# AnalogInterface2.net
KiCad netlist of a schematic drawn in Altium Designer
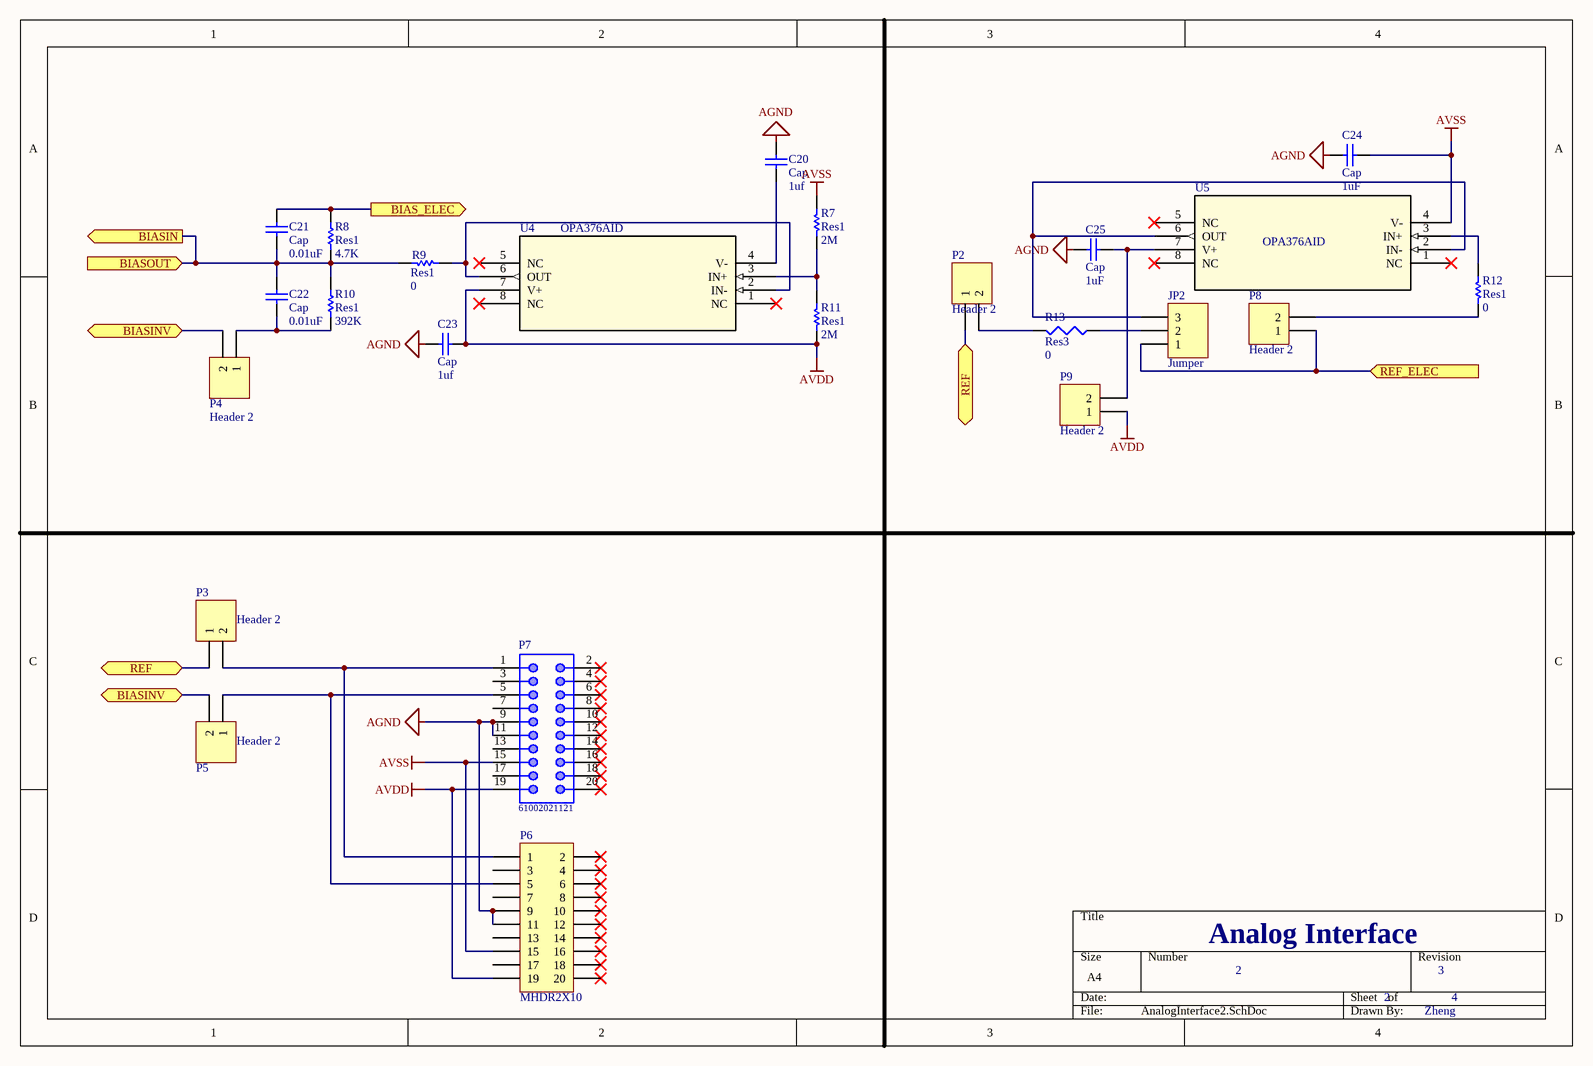
[diagram p0: AnalogInterface2.SchDoc]

(export (version "E")
  (design (tool "Eeschema 10.0.6"))
  (components
    (comp (ref "C20")
      (value "Cap")
      (footprint "0402C")
      (description "Capacitor")
      (fields (field (name "ALTIUM_VALUE") "1uf") (field (name "PUBLISHER") "Altium Limited"))
      (libsource (lib "Miscellaneous Devices") (part "Cap"))
    )
    (comp (ref "C21")
      (value "Cap")
      (footprint "0402C")
      (description "Capacitor")
      (fields (field (name "ALTIUM_VALUE") "0.01uF") (field (name "PUBLISHER") "Altium Limited"))
      (libsource (lib "Miscellaneous Devices") (part "Cap"))
    )
    (comp (ref "C22")
      (value "Cap")
      (footprint "0402C")
      (description "Capacitor")
      (fields (field (name "ALTIUM_VALUE") "0.01uF") (field (name "PUBLISHER") "Altium Limited"))
      (libsource (lib "Miscellaneous Devices") (part "Cap"))
    )
    (comp (ref "C23")
      (value "Cap")
      (footprint "0402C")
      (description "Capacitor")
      (fields (field (name "ALTIUM_VALUE") "1uf") (field (name "PUBLISHER") "Altium Limited"))
      (libsource (lib "Miscellaneous Devices") (part "Cap"))
    )
    (comp (ref "C24")
      (value "Cap")
      (footprint "0402C")
      (description "Capacitor")
      (fields (field (name "ALTIUM_VALUE") "1uF") (field (name "PUBLISHER") "Altium Limited"))
      (libsource (lib "Miscellaneous Devices") (part "Cap"))
    )
    (comp (ref "C25")
      (value "Cap")
      (footprint "0402C")
      (description "Capacitor")
      (fields (field (name "ALTIUM_VALUE") "1uF") (field (name "PUBLISHER") "Altium Limited"))
      (libsource (lib "Miscellaneous Devices") (part "Cap"))
    )
    (comp (ref "JP2")
      (value "Jumper")
      (footprint "HDR1X3")
      (description "Header, 3-Pin")
      (fields (field (name "PUBLISHER") "Altium Limited"))
      (libsource (lib "Miscellaneous Connectors") (part "Header 3"))
    )
    (comp (ref "P2")
      (value "Header 2")
      (footprint "HDR1X2")
      (description "Header, 2-Pin")
      (fields (field (name "PUBLISHER") "Altium Limited"))
      (libsource (lib "") (part "Header 2_2"))
    )
    (comp (ref "P3")
      (value "Header 2")
      (footprint "HDR1X2")
      (description "Header, 2-Pin")
      (fields (field (name "PUBLISHER") "Altium Limited"))
      (libsource (lib "") (part "Header 2_2"))
    )
    (comp (ref "P4")
      (value "Header 2")
      (footprint "HDR1X2")
      (description "Header, 2-Pin")
      (fields (field (name "PUBLISHER") "Altium Limited"))
      (libsource (lib "Miscellaneous Connectors") (part "Header 2"))
    )
    (comp (ref "P5")
      (value "Header 2")
      (footprint "HDR1X2")
      (description "Header, 2-Pin")
      (fields (field (name "PUBLISHER") "Altium Limited"))
      (libsource (lib "Miscellaneous Connectors") (part "Header 2"))
    )
    (comp (ref "P6")
      (value "MHDR2X10")
      (footprint "HDR2.54-M-LS-2x10P")
      (description "Header, 10-Pin, Dual row")
      (fields (field (name "PUBLISHER") "Altium Limited"))
      (libsource (lib "Miscellaneous Connectors") (part "MHDR2X10"))
    )
    (comp (ref "P7")
      (value "61002021121")
      (footprint "61002021121")
      (description "SMT Vertical Pin Header WR-PHD, Pitch 2.54 mm, Dual Row, 20 pins")
      (fields (field (name "PUBLISHER") "Wurth Elektronik"))
      (libsource (lib "Pin Header WR-PHD_2.54 mm") (part "61002021121"))
    )
    (comp (ref "P8")
      (value "Header 2")
      (footprint "HDR1X2")
      (description "Header, 2-Pin")
      (fields (field (name "PUBLISHER") "Altium Limited"))
      (libsource (lib "") (part "Header 2_1"))
    )
    (comp (ref "P9")
      (value "Header 2")
      (footprint "HDR1X2")
      (description "Header, 2-Pin")
      (fields (field (name "PUBLISHER") "Altium Limited"))
      (libsource (lib "") (part "Header 2_1"))
    )
    (comp (ref "R7")
      (value "Res1")
      (footprint "0603")
      (description "Resistor")
      (fields (field (name "ALTIUM_VALUE") "2M") (field (name "PUBLISHER") "Altium Limited"))
      (libsource (lib "Miscellaneous Devices") (part "Res1"))
    )
    (comp (ref "R8")
      (value "Res1")
      (footprint "0603")
      (description "Resistor")
      (fields (field (name "ALTIUM_VALUE") "4.7K") (field (name "PUBLISHER") "Altium Limited"))
      (libsource (lib "Miscellaneous Devices") (part "Res1"))
    )
    (comp (ref "R9")
      (value "Res1")
      (footprint "0603")
      (description "Resistor")
      (fields (field (name "ALTIUM_VALUE") "0") (field (name "PUBLISHER") "Altium Limited"))
      (libsource (lib "Miscellaneous Devices") (part "Res1"))
    )
    (comp (ref "R10")
      (value "Res1")
      (footprint "0603")
      (description "Resistor")
      (fields (field (name "ALTIUM_VALUE") "392K") (field (name "PUBLISHER") "Altium Limited"))
      (libsource (lib "Miscellaneous Devices") (part "Res1"))
    )
    (comp (ref "R11")
      (value "Res1")
      (footprint "0603")
      (description "Resistor")
      (fields (field (name "ALTIUM_VALUE") "2M") (field (name "PUBLISHER") "Altium Limited"))
      (libsource (lib "Miscellaneous Devices") (part "Res1"))
    )
    (comp (ref "R12")
      (value "Res1")
      (footprint "0603")
      (description "Resistor")
      (fields (field (name "ALTIUM_VALUE") "0") (field (name "PUBLISHER") "Altium Limited"))
      (libsource (lib "Miscellaneous Devices") (part "Res1"))
    )
    (comp (ref "R13")
      (value "Res3")
      (footprint "0603")
      (description "Resistor")
      (fields (field (name "ALTIUM_VALUE") "0") (field (name "PUBLISHER") "Altium Limited"))
      (libsource (lib "Miscellaneous Devices") (part "Res3"))
    )
    (comp (ref "U4")
      (value "OPA376AID")
      (footprint "SOIC8")
      (description "Precision, Low Noise, Low Iq Operational Amplifier")
      (fields
        (field (name "MANUFACTURER") "Texas Instruments")
        (field (name "GENERIC_PART_NUMBER") "OPA376")
        (field (name "COPYRIGHT") "Copyright (C) 2018 Accelerated Designs. All rights reserved")
      )
      (libsource (lib "2020-11-25_03-34-00") (part "OPA376AID"))
    )
    (comp (ref "U5")
      (value "OPA376AID")
      (footprint "SOIC8")
      (description "Precision, Low Noise, Low Iq Operational Amplifier")
      (fields
        (field (name "MANUFACTURER") "Texas Instruments")
        (field (name "GENERIC_PART_NUMBER") "OPA376")
        (field (name "COPYRIGHT") "Copyright (C) 2018 Accelerated Designs. All rights reserved")
      )
      (libsource (lib "2020-11-25_03-34-00") (part "OPA376AID"))
    )
  )
  (nets
    (net (code "1") (name "/BIASIN") (class "Default")
      (node (ref "C21") (pin "1") (pinfunction "1_1") (pintype "passive"))
      (node (ref "C22") (pin "2") (pinfunction "2_2") (pintype "passive"))
      (node (ref "R10") (pin "1") (pinfunction "1_1") (pintype "passive"))
      (node (ref "R8") (pin "2") (pinfunction "2_2") (pintype "passive"))
      (node (ref "R9") (pin "1") (pinfunction "1_1") (pintype "passive"))
    )
    (net (code "2") (name "/BIASINV") (class "Default")
      (node (ref "P4") (pin "2") (pinfunction "2_2") (pintype "passive"))
      (node (ref "P5") (pin "2") (pinfunction "2_2") (pintype "passive"))
    )
    (net (code "3") (name "/BIAS_ELEC") (class "Default")
      (node (ref "C21") (pin "2") (pinfunction "2_2") (pintype "passive"))
      (node (ref "R8") (pin "1") (pinfunction "1_1") (pintype "passive"))
    )
    (net (code "4") (name "/REF") (class "Default")
      (node (ref "P2") (pin "1") (pinfunction "1_1") (pintype "passive"))
      (node (ref "P3") (pin "1") (pinfunction "1_1") (pintype "passive"))
    )
    (net (code "5") (name "/REF_ELEC") (class "Default")
      (node (ref "JP2") (pin "1") (pinfunction "1_1") (pintype "passive"))
      (node (ref "P8") (pin "1") (pinfunction "1_1") (pintype "passive"))
    )
    (net (code "6") (name "AGND") (class "Default")
      (node (ref "C20") (pin "1") (pinfunction "1_1") (pintype "passive"))
      (node (ref "C23") (pin "1") (pinfunction "1_1") (pintype "passive"))
      (node (ref "C24") (pin "2") (pinfunction "2_2") (pintype "passive"))
      (node (ref "C25") (pin "2") (pinfunction "2_2") (pintype "passive"))
      (node (ref "P6") (pin "11") (pinfunction "11_11") (pintype "passive"))
      (node (ref "P6") (pin "9") (pinfunction "9_9") (pintype "passive"))
      (node (ref "P7") (pin "11") (pinfunction "11_11") (pintype "passive"))
      (node (ref "P7") (pin "9") (pinfunction "9_9") (pintype "passive"))
    )
    (net (code "7") (name "AVDD") (class "Default")
      (node (ref "C23") (pin "2") (pinfunction "2_2") (pintype "passive"))
      (node (ref "P6") (pin "19") (pinfunction "19_19") (pintype "passive"))
      (node (ref "P7") (pin "19") (pinfunction "19_19") (pintype "passive"))
      (node (ref "P9") (pin "1") (pinfunction "1_1") (pintype "passive"))
      (node (ref "R11") (pin "2") (pinfunction "2_2") (pintype "passive"))
      (node (ref "U4") (pin "7") (pinfunction "V+_7") (pintype "power_in"))
    )
    (net (code "8") (name "AVSS") (class "Default")
      (node (ref "C24") (pin "1") (pinfunction "1_1") (pintype "passive"))
      (node (ref "P6") (pin "15") (pinfunction "15_15") (pintype "passive"))
      (node (ref "P7") (pin "15") (pinfunction "15_15") (pintype "passive"))
      (node (ref "R7") (pin "1") (pinfunction "1_1") (pintype "passive"))
      (node (ref "U5") (pin "4") (pinfunction "V-_4") (pintype "power_in"))
    )
    (net (code "9") (name "Net-(C22-Pad1)") (class "Default")
      (node (ref "C22") (pin "1") (pinfunction "1_1") (pintype "passive"))
      (node (ref "P4") (pin "1") (pinfunction "1_1") (pintype "passive"))
      (node (ref "R10") (pin "2") (pinfunction "2_2") (pintype "passive"))
    )
    (net (code "10") (name "Net-(JP2-Pad2)") (class "Default")
      (node (ref "JP2") (pin "2") (pinfunction "2_2") (pintype "passive"))
      (node (ref "R13") (pin "2") (pinfunction "2_2") (pintype "passive"))
    )
    (net (code "11") (name "Net-(P2-Pad2)") (class "Default")
      (node (ref "P2") (pin "2") (pinfunction "2_2") (pintype "passive"))
      (node (ref "R13") (pin "1") (pinfunction "1_1") (pintype "passive"))
    )
    (net (code "12") (name "Net-(P3-Pad2)") (class "Default")
      (node (ref "P3") (pin "2") (pinfunction "2_2") (pintype "passive"))
      (node (ref "P6") (pin "1") (pinfunction "1_1") (pintype "passive"))
      (node (ref "P7") (pin "1") (pinfunction "1_1") (pintype "passive"))
    )
    (net (code "13") (name "Net-(P5-Pad1)") (class "Default")
      (node (ref "P5") (pin "1") (pinfunction "1_1") (pintype "passive"))
      (node (ref "P6") (pin "5") (pinfunction "5_5") (pintype "passive"))
      (node (ref "P7") (pin "5") (pinfunction "5_5") (pintype "passive"))
    )
    (net (code "14") (name "Net-(P8-Pad2)") (class "Default")
      (node (ref "P8") (pin "2") (pinfunction "2_2") (pintype "passive"))
      (node (ref "R12") (pin "1") (pinfunction "1_1") (pintype "passive"))
    )
    (net (code "15") (name "Net-(U4-IN+)") (class "Default")
      (node (ref "R11") (pin "1") (pinfunction "1_1") (pintype "passive"))
      (node (ref "R7") (pin "2") (pinfunction "2_2") (pintype "passive"))
      (node (ref "U4") (pin "3") (pinfunction "IN+_3") (pintype "input"))
    )
    (net (code "16") (name "Net-(U4-IN-)") (class "Default")
      (node (ref "R9") (pin "2") (pinfunction "2_2") (pintype "passive"))
      (node (ref "U4") (pin "2") (pinfunction "IN-_2") (pintype "input"))
      (node (ref "U4") (pin "6") (pinfunction "OUT_6") (pintype "output"))
    )
    (net (code "17") (name "Net-(U4-V-)") (class "Default")
      (node (ref "C20") (pin "2") (pinfunction "2_2") (pintype "passive"))
      (node (ref "U4") (pin "4") (pinfunction "V-_4") (pintype "power_in"))
    )
    (net (code "18") (name "Net-(U5-IN+)") (class "Default")
      (node (ref "R12") (pin "2") (pinfunction "2_2") (pintype "passive"))
      (node (ref "U5") (pin "3") (pinfunction "IN+_3") (pintype "input"))
    )
    (net (code "19") (name "Net-(U5-IN-)") (class "Default")
      (node (ref "JP2") (pin "3") (pinfunction "3_3") (pintype "passive"))
      (node (ref "U5") (pin "2") (pinfunction "IN-_2") (pintype "input"))
      (node (ref "U5") (pin "6") (pinfunction "OUT_6") (pintype "output"))
    )
    (net (code "20") (name "Net-(U5-V+)") (class "Default")
      (node (ref "C25") (pin "1") (pinfunction "1_1") (pintype "passive"))
      (node (ref "P9") (pin "2") (pinfunction "2_2") (pintype "passive"))
      (node (ref "U5") (pin "7") (pinfunction "V+_7") (pintype "power_in"))
    )
    (net (code "21") (name "unconnected-(P6-Pad2)") (class "Default")
      (node (ref "P6") (pin "2") (pinfunction "2_2") (pintype "passive+no_connect"))
    )
    (net (code "22") (name "unconnected-(P6-Pad3)") (class "Default")
      (node (ref "P6") (pin "3") (pinfunction "3_3") (pintype "passive"))
    )
    (net (code "23") (name "unconnected-(P6-Pad4)") (class "Default")
      (node (ref "P6") (pin "4") (pinfunction "4_4") (pintype "passive+no_connect"))
    )
    (net (code "24") (name "unconnected-(P6-Pad6)") (class "Default")
      (node (ref "P6") (pin "6") (pinfunction "6_6") (pintype "passive+no_connect"))
    )
    (net (code "25") (name "unconnected-(P6-Pad7)") (class "Default")
      (node (ref "P6") (pin "7") (pinfunction "7_7") (pintype "passive"))
    )
    (net (code "26") (name "unconnected-(P6-Pad8)") (class "Default")
      (node (ref "P6") (pin "8") (pinfunction "8_8") (pintype "passive+no_connect"))
    )
    (net (code "27") (name "unconnected-(P6-Pad10)") (class "Default")
      (node (ref "P6") (pin "10") (pinfunction "10_10") (pintype "passive+no_connect"))
    )
    (net (code "28") (name "unconnected-(P6-Pad12)") (class "Default")
      (node (ref "P6") (pin "12") (pinfunction "12_12") (pintype "passive+no_connect"))
    )
    (net (code "29") (name "unconnected-(P6-Pad13)") (class "Default")
      (node (ref "P6") (pin "13") (pinfunction "13_13") (pintype "passive"))
    )
    (net (code "30") (name "unconnected-(P6-Pad14)") (class "Default")
      (node (ref "P6") (pin "14") (pinfunction "14_14") (pintype "passive+no_connect"))
    )
    (net (code "31") (name "unconnected-(P6-Pad16)") (class "Default")
      (node (ref "P6") (pin "16") (pinfunction "16_16") (pintype "passive+no_connect"))
    )
    (net (code "32") (name "unconnected-(P6-Pad17)") (class "Default")
      (node (ref "P6") (pin "17") (pinfunction "17_17") (pintype "passive"))
    )
    (net (code "33") (name "unconnected-(P6-Pad18)") (class "Default")
      (node (ref "P6") (pin "18") (pinfunction "18_18") (pintype "passive+no_connect"))
    )
    (net (code "34") (name "unconnected-(P6-Pad20)") (class "Default")
      (node (ref "P6") (pin "20") (pinfunction "20_20") (pintype "passive+no_connect"))
    )
    (net (code "35") (name "unconnected-(P7-Pad2)") (class "Default")
      (node (ref "P7") (pin "2") (pinfunction "2_2") (pintype "passive+no_connect"))
    )
    (net (code "36") (name "unconnected-(P7-Pad3)") (class "Default")
      (node (ref "P7") (pin "3") (pinfunction "3_3") (pintype "passive"))
    )
    (net (code "37") (name "unconnected-(P7-Pad4)") (class "Default")
      (node (ref "P7") (pin "4") (pinfunction "4_4") (pintype "passive+no_connect"))
    )
    (net (code "38") (name "unconnected-(P7-Pad6)") (class "Default")
      (node (ref "P7") (pin "6") (pinfunction "6_6") (pintype "passive+no_connect"))
    )
    (net (code "39") (name "unconnected-(P7-Pad7)") (class "Default")
      (node (ref "P7") (pin "7") (pinfunction "7_7") (pintype "passive"))
    )
    (net (code "40") (name "unconnected-(P7-Pad8)") (class "Default")
      (node (ref "P7") (pin "8") (pinfunction "8_8") (pintype "passive+no_connect"))
    )
    (net (code "41") (name "unconnected-(P7-Pad10)") (class "Default")
      (node (ref "P7") (pin "10") (pinfunction "10_10") (pintype "passive+no_connect"))
    )
    (net (code "42") (name "unconnected-(P7-Pad12)") (class "Default")
      (node (ref "P7") (pin "12") (pinfunction "12_12") (pintype "passive+no_connect"))
    )
    (net (code "43") (name "unconnected-(P7-Pad13)") (class "Default")
      (node (ref "P7") (pin "13") (pinfunction "13_13") (pintype "passive"))
    )
    (net (code "44") (name "unconnected-(P7-Pad14)") (class "Default")
      (node (ref "P7") (pin "14") (pinfunction "14_14") (pintype "passive+no_connect"))
    )
    (net (code "45") (name "unconnected-(P7-Pad16)") (class "Default")
      (node (ref "P7") (pin "16") (pinfunction "16_16") (pintype "passive+no_connect"))
    )
    (net (code "46") (name "unconnected-(P7-Pad17)") (class "Default")
      (node (ref "P7") (pin "17") (pinfunction "17_17") (pintype "passive"))
    )
    (net (code "47") (name "unconnected-(P7-Pad18)") (class "Default")
      (node (ref "P7") (pin "18") (pinfunction "18_18") (pintype "passive+no_connect"))
    )
    (net (code "48") (name "unconnected-(P7-Pad20)") (class "Default")
      (node (ref "P7") (pin "20") (pinfunction "20_20") (pintype "passive+no_connect"))
    )
    (net (code "49") (name "unconnected-(U4-NC-Pad1)") (class "Default")
      (node (ref "U4") (pin "1") (pinfunction "NC_1") (pintype "passive+no_connect"))
    )
    (net (code "50") (name "unconnected-(U4-NC-Pad5)") (class "Default")
      (node (ref "U4") (pin "5") (pinfunction "NC_5") (pintype "passive+no_connect"))
    )
    (net (code "51") (name "unconnected-(U4-NC-Pad8)") (class "Default")
      (node (ref "U4") (pin "8") (pinfunction "NC_8") (pintype "passive+no_connect"))
    )
    (net (code "52") (name "unconnected-(U5-NC-Pad1)") (class "Default")
      (node (ref "U5") (pin "1") (pinfunction "NC_1") (pintype "passive+no_connect"))
    )
    (net (code "53") (name "unconnected-(U5-NC-Pad5)") (class "Default")
      (node (ref "U5") (pin "5") (pinfunction "NC_5") (pintype "passive+no_connect"))
    )
    (net (code "54") (name "unconnected-(U5-NC-Pad8)") (class "Default")
      (node (ref "U5") (pin "8") (pinfunction "NC_8") (pintype "passive+no_connect"))
    )
  )
)
